# GymkhanaStoper_v1_6.net
KiCad netlist of a schematic drawn in Altium Designer
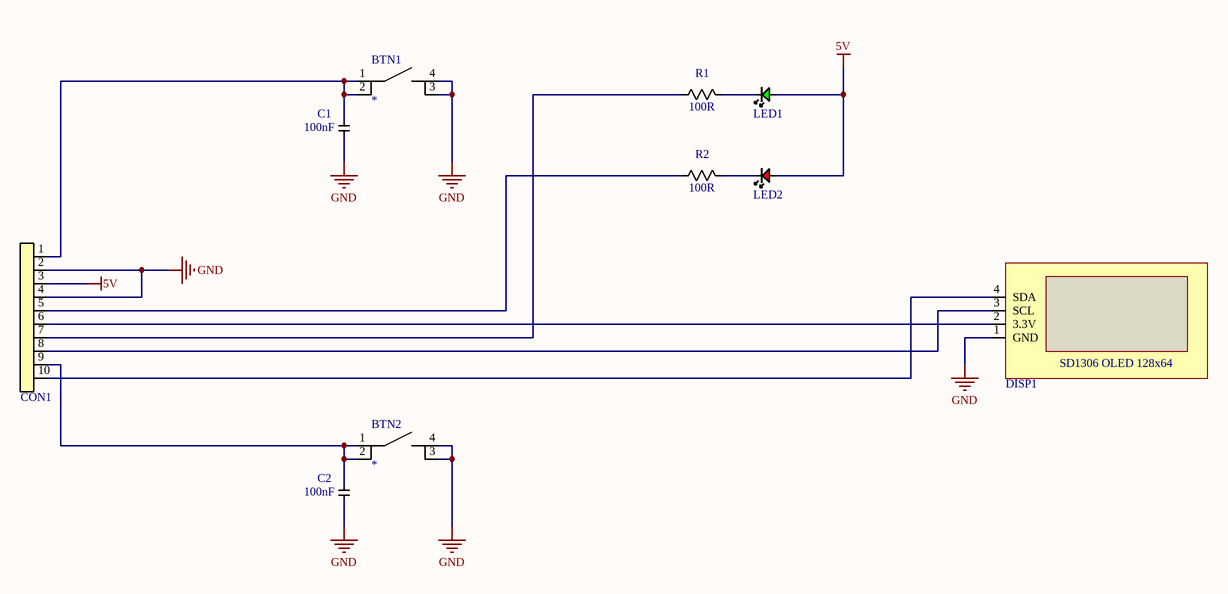
[diagram p0: GymkhanaStoper v1.6.SchDoc]

(export (version "E")
  (design (tool "Eeschema 10.0.6"))
  (components
    (comp (ref "BTN1") (value "*") (footprint "TACT12x12") (libsource (lib "Przyciski") (part "TACT12x12")))
    (comp (ref "BTN2") (value "*") (footprint "TACT12x12") (libsource (lib "Przyciski") (part "TACT12x12")))
    (comp (ref "C1")
      (value "kondensator")
      (footprint "0805-C")
      (fields (field (name "POJEMNOŚĆ") "100nF"))
      (libsource (lib "C") (part "C"))
    )
    (comp (ref "C2")
      (value "kondensator")
      (footprint "0805-C")
      (fields (field (name "POJEMNOŚĆ") "100nF"))
      (libsource (lib "C") (part "C"))
    )
    (comp (ref "CON1")
      (value "*")
      (footprint "IDC10_2.54mm_SMT")
      (libsource (lib "Konektory") (part "IDC10_2.54mm"))
    )
    (comp (ref "DISP1")
      (value "*")
      (footprint "SD1306-128x64 nohole")
      (description "SD1306_128x64")
      (libsource (lib "Wyswietlacze") (part "SD1306_128x64"))
    )
    (comp (ref "LED1")
      (value "*")
      (footprint "LED5mm_plaska_GREEN")
      (description "Led zielona")
      (libsource (lib "D") (part "Led5mm_green"))
    )
    (comp (ref "LED2")
      (value "*")
      (footprint "LED5mm_plaska_RED")
      (description "Led czerwona")
      (libsource (lib "D") (part "Led5mm_red"))
    )
    (comp (ref "R1")
      (value "rezystor")
      (footprint "0805-R")
      (fields (field (name "REZYSTANCJA") "100R"))
      (libsource (lib "R") (part "R"))
    )
    (comp (ref "R2")
      (value "rezystor")
      (footprint "0805-R")
      (fields (field (name "REZYSTANCJA") "100R"))
      (libsource (lib "R") (part "R"))
    )
  )
  (nets
    (net (code "1") (name "5V") (class "Default")
      (node (ref "CON1") (pin "3") (pinfunction "3_3") (pintype "passive"))
      (node (ref "LED1") (pin "1") (pinfunction "A_1") (pintype "passive"))
      (node (ref "LED2") (pin "1") (pinfunction "A_1") (pintype "passive"))
    )
    (net (code "2") (name "GND") (class "Default")
      (node (ref "BTN1") (pin "3") (pinfunction "3_3") (pintype "passive"))
      (node (ref "BTN1") (pin "4") (pinfunction "4_4") (pintype "passive"))
      (node (ref "BTN2") (pin "3") (pinfunction "3_3") (pintype "passive"))
      (node (ref "BTN2") (pin "4") (pinfunction "4_4") (pintype "passive"))
      (node (ref "C1") (pin "1") (pinfunction "1_1") (pintype "passive"))
      (node (ref "C2") (pin "1") (pinfunction "1_1") (pintype "passive"))
      (node (ref "CON1") (pin "2") (pinfunction "1_2") (pintype "passive"))
      (node (ref "CON1") (pin "4") (pinfunction "4_4") (pintype "passive"))
      (node (ref "DISP1") (pin "1") (pinfunction "GND_1") (pintype "passive"))
    )
    (net (code "3") (name "Net-(BTN1-Pad1)") (class "Default")
      (node (ref "BTN1") (pin "1") (pinfunction "1_1") (pintype "passive"))
      (node (ref "BTN1") (pin "2") (pinfunction "2_2") (pintype "passive"))
      (node (ref "C1") (pin "2") (pinfunction "2_2") (pintype "passive"))
      (node (ref "CON1") (pin "1") (pinfunction "1_1") (pintype "passive"))
    )
    (net (code "4") (name "Net-(BTN2-Pad1)") (class "Default")
      (node (ref "BTN2") (pin "1") (pinfunction "1_1") (pintype "passive"))
      (node (ref "BTN2") (pin "2") (pinfunction "2_2") (pintype "passive"))
      (node (ref "C2") (pin "2") (pinfunction "2_2") (pintype "passive"))
      (node (ref "CON1") (pin "9") (pinfunction "9_9") (pintype "passive"))
    )
    (net (code "5") (name "Net-(CON1-Pad5)") (class "Default")
      (node (ref "CON1") (pin "5") (pinfunction "5_5") (pintype "passive"))
      (node (ref "R2") (pin "1") (pinfunction "1_1") (pintype "passive"))
    )
    (net (code "6") (name "Net-(CON1-Pad7)") (class "Default")
      (node (ref "CON1") (pin "7") (pinfunction "7_7") (pintype "passive"))
      (node (ref "R1") (pin "1") (pinfunction "1_1") (pintype "passive"))
    )
    (net (code "7") (name "Net-(DISP1-3.3V)") (class "Default")
      (node (ref "CON1") (pin "6") (pinfunction "6_6") (pintype "passive"))
      (node (ref "DISP1") (pin "2") (pinfunction "3.3V_2") (pintype "passive"))
    )
    (net (code "8") (name "Net-(DISP1-SCL)") (class "Default")
      (node (ref "CON1") (pin "8") (pinfunction "8_8") (pintype "passive"))
      (node (ref "DISP1") (pin "3") (pinfunction "SCL_3") (pintype "passive"))
    )
    (net (code "9") (name "Net-(DISP1-SDA)") (class "Default")
      (node (ref "CON1") (pin "10") (pinfunction "10_10") (pintype "passive"))
      (node (ref "DISP1") (pin "4") (pinfunction "SDA_4") (pintype "passive"))
    )
    (net (code "10") (name "Net-(LED1-K)") (class "Default")
      (node (ref "LED1") (pin "2") (pinfunction "K_2") (pintype "passive"))
      (node (ref "R1") (pin "2") (pinfunction "2_2") (pintype "passive"))
    )
    (net (code "11") (name "Net-(LED2-K)") (class "Default")
      (node (ref "LED2") (pin "2") (pinfunction "K_2") (pintype "passive"))
      (node (ref "R2") (pin "2") (pinfunction "2_2") (pintype "passive"))
    )
  )
)
